# Z21_MEGA_2.net
KiCad netlist of a schematic drawn in EAGLE
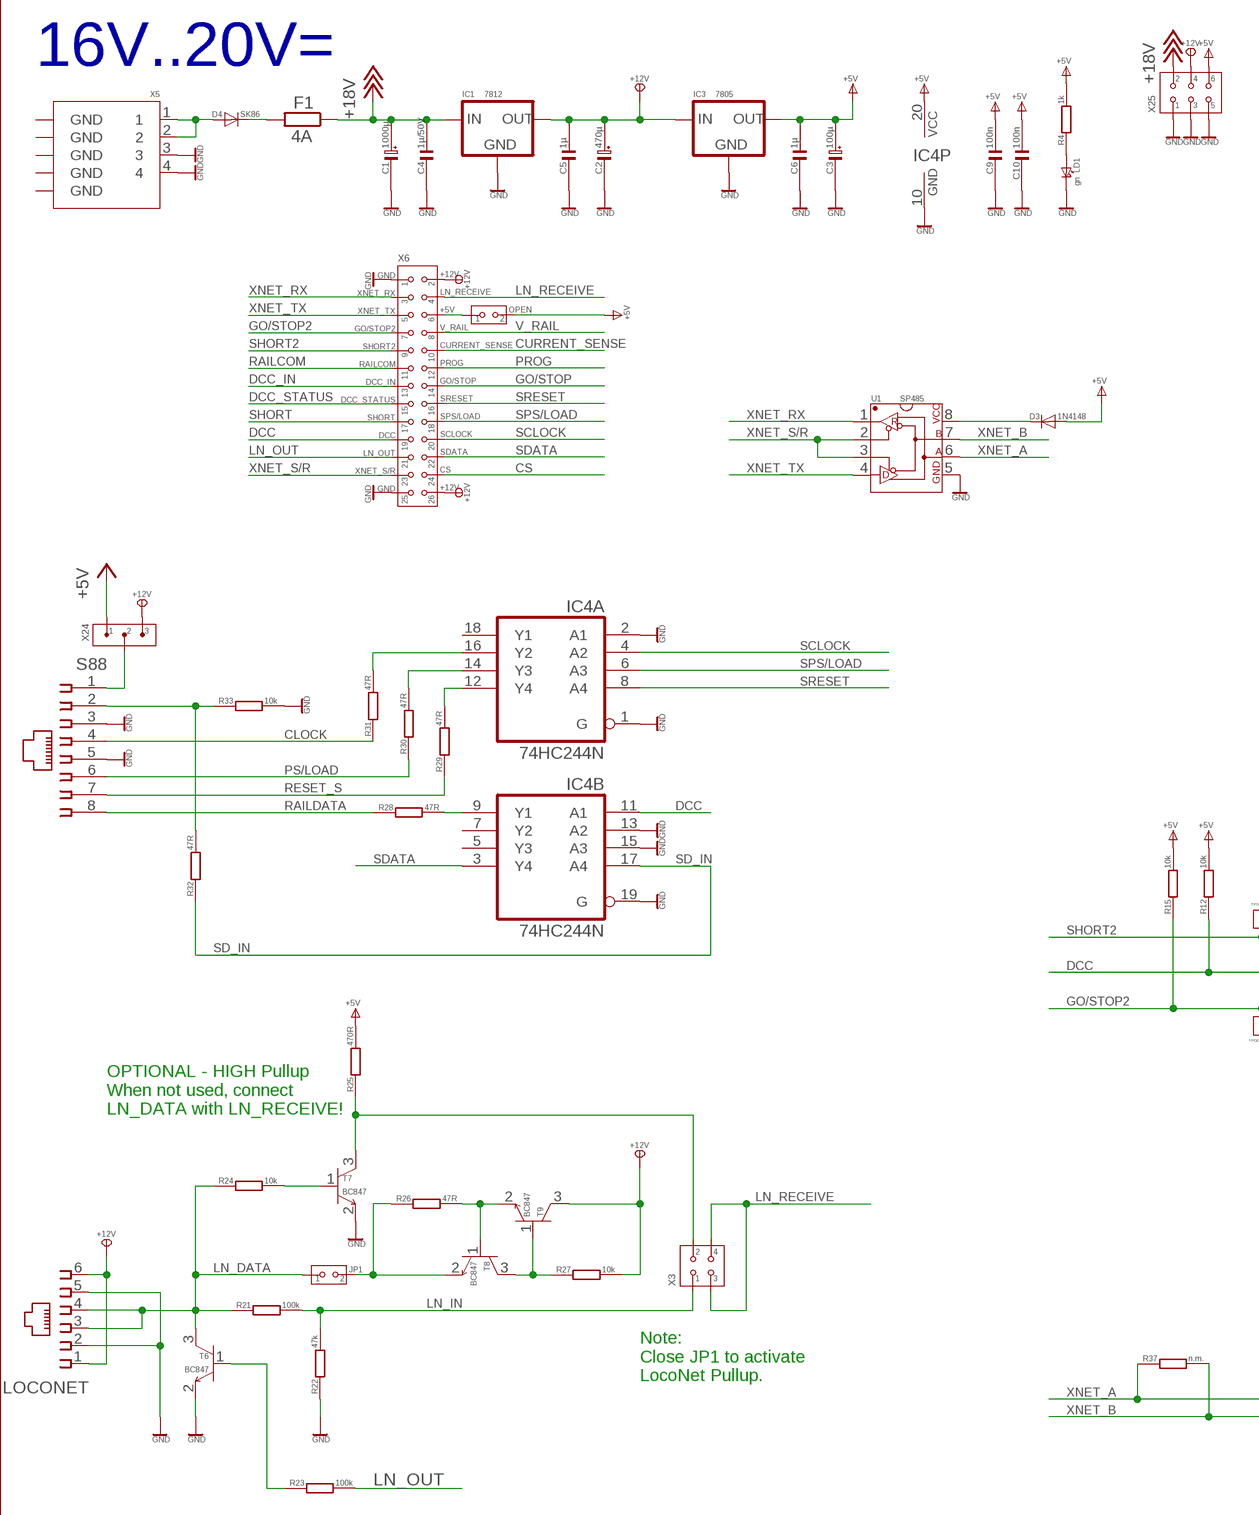
[diagram p0: schematic, sheet 1, part 1 of 2]
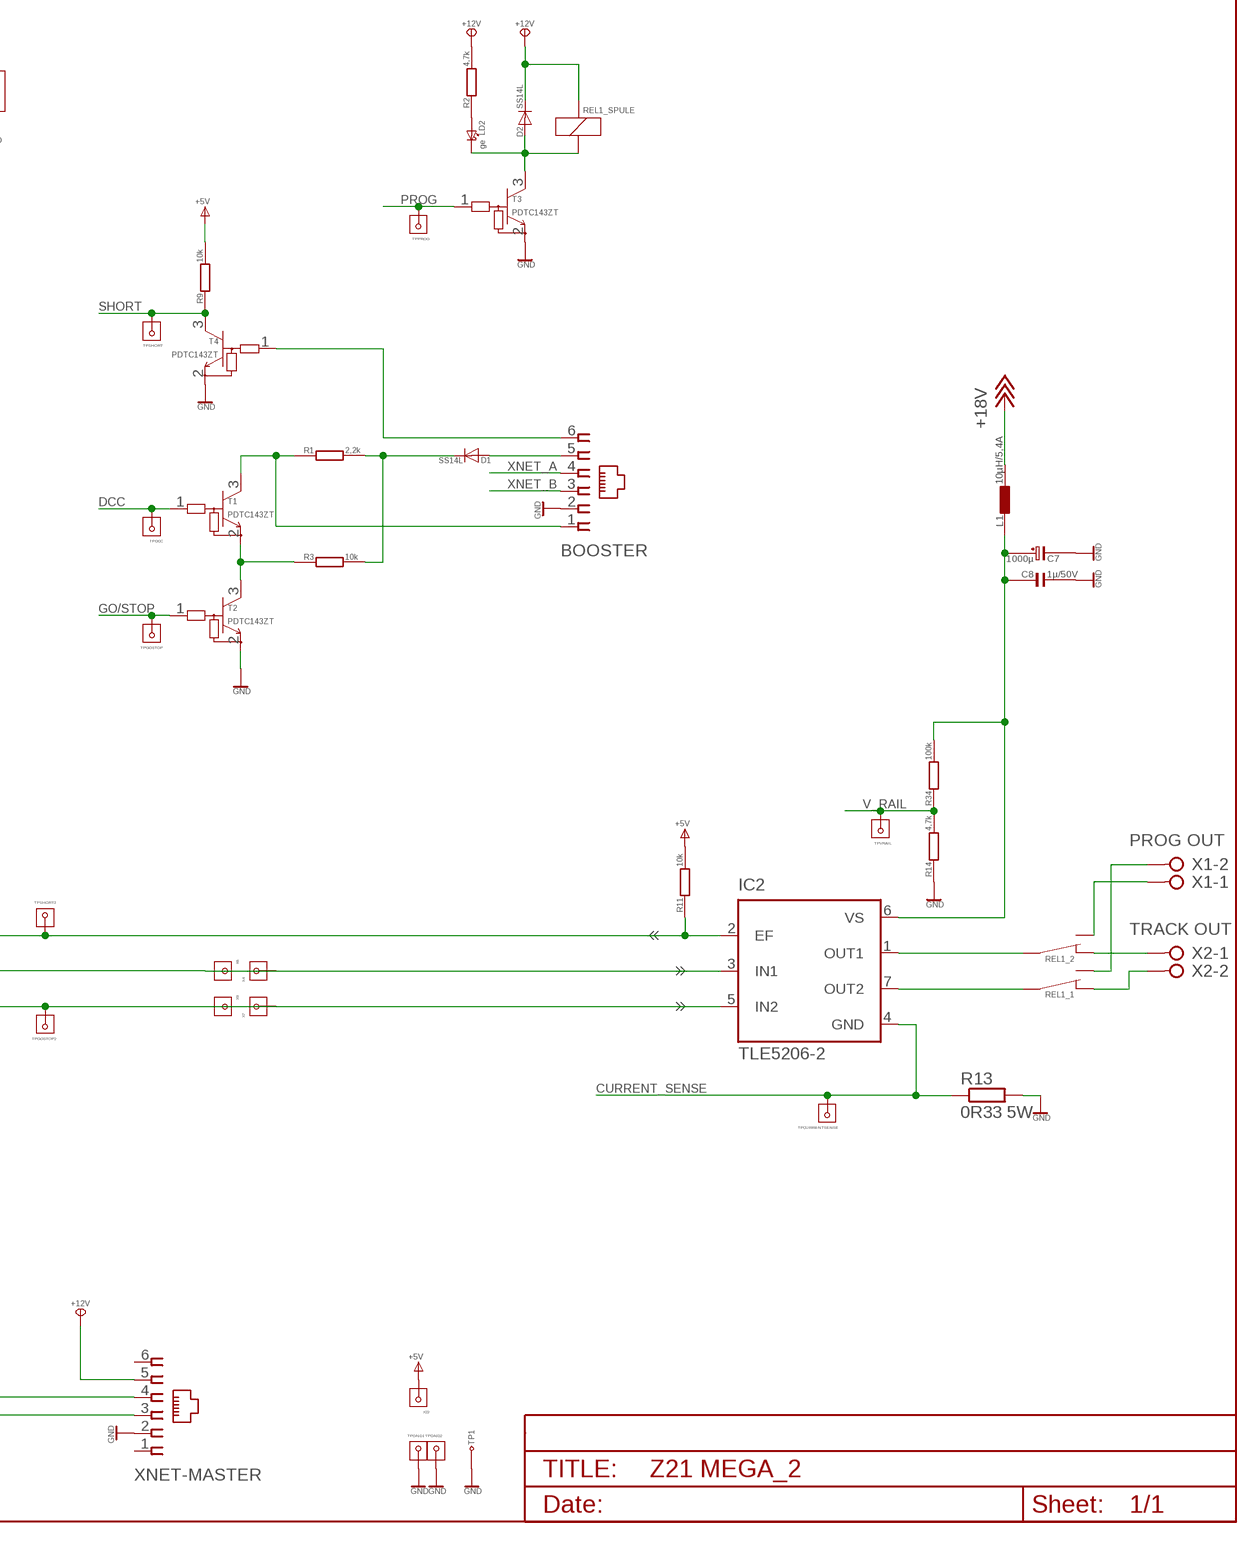
[diagram p1: schematic, sheet 1, part 2 of 2]

(export (version "E")
  (design (tool "Eeschema 10.0.6"))
  (components
    (comp (ref "BOOSTER")
      (value "520250-3")
      (footprint "eagle-import:520250-3")
      (libsource (lib "eagle-import") (part "520250-3"))
    )
    (comp (ref "C1")
      (value "1000µ")
      (footprint "eagle-import:RM5_DIA12.5")
      (libsource (lib "eagle-import") (part "ELKORM5_DIA12.5"))
    )
    (comp (ref "C2")
      (value "470µ")
      (footprint "eagle-import:RM5_DIA10")
      (libsource (lib "eagle-import") (part "ELKORM5_DIA10"))
    )
    (comp (ref "C3")
      (value "100µ")
      (footprint "eagle-import:RM2.5_DIA6")
      (libsource (lib "eagle-import") (part "ELKORM2.5_DIA6"))
    )
    (comp (ref "C4")
      (value "1µ/50V")
      (footprint "eagle-import:C0805")
      (libsource (lib "eagle-import") (part "C0805"))
    )
    (comp (ref "C5")
      (value "1µ")
      (footprint "eagle-import:C0805")
      (libsource (lib "eagle-import") (part "C0805"))
    )
    (comp (ref "C6")
      (value "1µ")
      (footprint "eagle-import:C0805")
      (libsource (lib "eagle-import") (part "C0805"))
    )
    (comp (ref "C7")
      (value "1000µ")
      (footprint "eagle-import:RM5_DIA12.5")
      (libsource (lib "eagle-import") (part "ELKORM5_DIA12.5"))
    )
    (comp (ref "C8")
      (value "1µ/50V")
      (footprint "eagle-import:C0805")
      (libsource (lib "eagle-import") (part "C0805"))
    )
    (comp (ref "C9")
      (value "100n")
      (footprint "eagle-import:C0805")
      (libsource (lib "eagle-import") (part "C0805"))
    )
    (comp (ref "C10")
      (value "100n")
      (footprint "eagle-import:C0805")
      (libsource (lib "eagle-import") (part "C0805"))
    )
    (comp (ref "D1")
      (value "SS14L")
      (footprint "eagle-import:SUB-SMA_")
      (libsource (lib "eagle-import") (part "DIODESUB-SMA_"))
    )
    (comp (ref "D2")
      (value "SS14L")
      (footprint "eagle-import:SUB-SMA_")
      (libsource (lib "eagle-import") (part "DIODESUB-SMA_"))
    )
    (comp (ref "D3")
      (value "1N4148")
      (footprint "eagle-import:SOD323_")
      (libsource (lib "eagle-import") (part "DIODESOD323"))
    )
    (comp (ref "D4")
      (value "SK86")
      (footprint "eagle-import:SMC_")
      (libsource (lib "eagle-import") (part "DIODESMC_"))
    )
    (comp (ref "F1")
      (value "4A")
      (footprint "eagle-import:0204_5")
      (libsource (lib "eagle-import") (part "R-EU_0204/5"))
    )
    (comp (ref "IC1")
      (value "7812")
      (footprint "eagle-import:78XXS")
      (libsource (lib "eagle-import") (part "78XXLSTEHEND"))
    )
    (comp (ref "IC2")
      (value "TLE5206-2")
      (footprint "eagle-import:P-TO220-7-11")
      (libsource (lib "eagle-import") (part "TLE5205-2"))
    )
    (comp (ref "IC3")
      (value "7805")
      (footprint "eagle-import:78XXS")
      (libsource (lib "eagle-import") (part "78XXLSTEHEND"))
    )
    (comp (ref "IC4")
      (value "74HC244N")
      (footprint "eagle-import:DIL20")
      (libsource (lib "eagle-import") (part "74244NHC"))
    )
    (comp (ref "JP1")
      (value "1X02_JUMPER_2.54MM")
      (footprint "eagle-import:1X02_2.54MM")
      (libsource (lib "eagle-import") (part "1X02_JUMPER_2.54MM"))
    )
    (comp (ref "L1")
      (value "10µH/5,4A")
      (footprint "eagle-import:12,5X12,5MM")
      (libsource (lib "eagle-import") (part "L12,5X12,5MM"))
    )
    (comp (ref "LD1")
      (value "gn")
      (footprint "eagle-import:LED3MM_")
      (libsource (lib "eagle-import") (part "LED3MM_"))
    )
    (comp (ref "LD2")
      (value "ge")
      (footprint "eagle-import:LED3MM_")
      (libsource (lib "eagle-import") (part "LED3MM_"))
    )
    (comp (ref "LOCONET")
      (value "520250-3")
      (footprint "eagle-import:520250-3")
      (libsource (lib "eagle-import") (part "520250-3"))
    )
    (comp (ref "OPEN")
      (value "1X02_JUMPER_2.54MM")
      (footprint "eagle-import:1X02_2.54MM")
      (libsource (lib "eagle-import") (part "1X02_JUMPER_2.54MM"))
    )
    (comp (ref "R1")
      (value "2,2k")
      (footprint "eagle-import:R0805")
      (libsource (lib "eagle-import") (part "R0805"))
    )
    (comp (ref "R2")
      (value "4,7k")
      (footprint "eagle-import:R0805")
      (libsource (lib "eagle-import") (part "R0805"))
    )
    (comp (ref "R3")
      (value "10k")
      (footprint "eagle-import:R0805")
      (libsource (lib "eagle-import") (part "R0805"))
    )
    (comp (ref "R4")
      (value "1k")
      (footprint "eagle-import:R0805")
      (libsource (lib "eagle-import") (part "R0805"))
    )
    (comp (ref "R9")
      (value "10k")
      (footprint "eagle-import:R0805")
      (libsource (lib "eagle-import") (part "R0805"))
    )
    (comp (ref "R11")
      (value "10k")
      (footprint "eagle-import:R0805")
      (libsource (lib "eagle-import") (part "R0805"))
    )
    (comp (ref "R12")
      (value "10k")
      (footprint "eagle-import:R0805")
      (libsource (lib "eagle-import") (part "R0805"))
    )
    (comp (ref "R13")
      (value "0R33 5W")
      (footprint "eagle-import:VMTA55")
      (libsource (lib "eagle-import") (part "R-EU_VMTA55"))
    )
    (comp (ref "R14")
      (value "4,7k")
      (footprint "eagle-import:R0805")
      (libsource (lib "eagle-import") (part "R0805"))
    )
    (comp (ref "R15")
      (value "10k")
      (footprint "eagle-import:R0805")
      (libsource (lib "eagle-import") (part "R0805"))
    )
    (comp (ref "R21")
      (value "100k")
      (footprint "eagle-import:R0805")
      (libsource (lib "eagle-import") (part "R0805"))
    )
    (comp (ref "R22")
      (value "47k")
      (footprint "eagle-import:R0805")
      (libsource (lib "eagle-import") (part "R0805"))
    )
    (comp (ref "R23")
      (value "100k")
      (footprint "eagle-import:R0805")
      (libsource (lib "eagle-import") (part "R0805"))
    )
    (comp (ref "R24")
      (value "10k")
      (footprint "eagle-import:R0805")
      (libsource (lib "eagle-import") (part "R0805"))
    )
    (comp (ref "R25")
      (value "470R")
      (footprint "eagle-import:R0805")
      (libsource (lib "eagle-import") (part "R0805"))
    )
    (comp (ref "R26")
      (value "47R")
      (footprint "eagle-import:R0805")
      (libsource (lib "eagle-import") (part "R0805"))
    )
    (comp (ref "R27")
      (value "10k")
      (footprint "eagle-import:R0805")
      (libsource (lib "eagle-import") (part "R0805"))
    )
    (comp (ref "R28")
      (value "47R")
      (footprint "eagle-import:R0805")
      (libsource (lib "eagle-import") (part "R0805"))
    )
    (comp (ref "R29")
      (value "47R")
      (footprint "eagle-import:R0805")
      (libsource (lib "eagle-import") (part "R0805"))
    )
    (comp (ref "R30")
      (value "47R")
      (footprint "eagle-import:R0805")
      (libsource (lib "eagle-import") (part "R0805"))
    )
    (comp (ref "R31")
      (value "47R")
      (footprint "eagle-import:R0805")
      (libsource (lib "eagle-import") (part "R0805"))
    )
    (comp (ref "R32")
      (value "47R")
      (footprint "eagle-import:R0805")
      (libsource (lib "eagle-import") (part "R0805"))
    )
    (comp (ref "R33")
      (value "10k")
      (footprint "eagle-import:R0805")
      (libsource (lib "eagle-import") (part "R0805"))
    )
    (comp (ref "R34")
      (value "100k")
      (footprint "eagle-import:R0805")
      (libsource (lib "eagle-import") (part "R0805"))
    )
    (comp (ref "R37")
      (value "n.m.")
      (footprint "eagle-import:R0805")
      (libsource (lib "eagle-import") (part "R0805"))
    )
    (comp (ref "REL1")
      (value "DIL16_1FINDER_40.527")
      (footprint "eagle-import:FINDER_40.527")
      (libsource (lib "eagle-import") (part "DIL16_1FINDER_40.527"))
    )
    (comp (ref "S88")
      (value "520251-4")
      (footprint "eagle-import:520251-4")
      (libsource (lib "eagle-import") (part "520251-4"))
    )
    (comp (ref "T1")
      (value "PDTC143ZT")
      (footprint "eagle-import:SOT23_")
      (libsource (lib "eagle-import") (part "NPN_PRE-BIASED"))
    )
    (comp (ref "T2")
      (value "PDTC143ZT")
      (footprint "eagle-import:SOT23_")
      (libsource (lib "eagle-import") (part "NPN_PRE-BIASED"))
    )
    (comp (ref "T3")
      (value "PDTC143ZT")
      (footprint "eagle-import:SOT23_")
      (libsource (lib "eagle-import") (part "NPN_PRE-BIASED"))
    )
    (comp (ref "T4")
      (value "PDTC143ZT")
      (footprint "eagle-import:SOT23_")
      (libsource (lib "eagle-import") (part "NPN_PRE-BIASED"))
    )
    (comp (ref "T6")
      (value "BC847")
      (footprint "eagle-import:SOT23_")
      (libsource (lib "eagle-import") (part "NPNSOT23"))
    )
    (comp (ref "T7")
      (value "BC847")
      (footprint "eagle-import:SOT23_")
      (libsource (lib "eagle-import") (part "NPNSOT23"))
    )
    (comp (ref "T8")
      (value "BC847")
      (footprint "eagle-import:SOT23_")
      (libsource (lib "eagle-import") (part "NPNSOT23"))
    )
    (comp (ref "T9")
      (value "BC847")
      (footprint "eagle-import:SOT23_")
      (libsource (lib "eagle-import") (part "NPNSOT23"))
    )
    (comp (ref "TP1")
      (value "LÖTPUNKTTHT_1.3MM_51.2MIL")
      (footprint "eagle-import:THT_1.3MM_51.2MIL")
      (libsource (lib "eagle-import") (part "LÖTPUNKTTHT_1.3MM_51.2MIL"))
    )
    (comp (ref "TPCURRENTSENSE")
      (value "1X01_2.54MM")
      (footprint "eagle-import:1X01_2.54MM")
      (libsource (lib "eagle-import") (part "1X01_2.54MM"))
    )
    (comp (ref "TPDCC")
      (value "1X01_2.54MM")
      (footprint "eagle-import:1X01_2.54MM")
      (libsource (lib "eagle-import") (part "1X01_2.54MM"))
    )
    (comp (ref "TPGND1")
      (value "1X01_2.54MM")
      (footprint "eagle-import:1X01_2.54MM")
      (libsource (lib "eagle-import") (part "1X01_2.54MM"))
    )
    (comp (ref "TPGND2")
      (value "1X01_2.54MM")
      (footprint "eagle-import:1X01_2.54MM")
      (libsource (lib "eagle-import") (part "1X01_2.54MM"))
    )
    (comp (ref "TPGOSTOP")
      (value "1X01_2.54MM")
      (footprint "eagle-import:1X01_2.54MM")
      (libsource (lib "eagle-import") (part "1X01_2.54MM"))
    )
    (comp (ref "TPGOSTOP2")
      (value "1X01_2.54MM")
      (footprint "eagle-import:1X01_2.54MM")
      (libsource (lib "eagle-import") (part "1X01_2.54MM"))
    )
    (comp (ref "TPPROG")
      (value "1X01_2.54MM")
      (footprint "eagle-import:1X01_2.54MM")
      (libsource (lib "eagle-import") (part "1X01_2.54MM"))
    )
    (comp (ref "TPSHORT")
      (value "1X01_2.54MM")
      (footprint "eagle-import:1X01_2.54MM")
      (libsource (lib "eagle-import") (part "1X01_2.54MM"))
    )
    (comp (ref "TPSHORT2")
      (value "1X01_2.54MM")
      (footprint "eagle-import:1X01_2.54MM")
      (libsource (lib "eagle-import") (part "1X01_2.54MM"))
    )
    (comp (ref "TPVRAIL")
      (value "1X01_2.54MM")
      (footprint "eagle-import:1X01_2.54MM")
      (libsource (lib "eagle-import") (part "1X01_2.54MM"))
    )
    (comp (ref "U1")
      (value "SP485")
      (footprint "eagle-import:SO8__")
      (libsource (lib "eagle-import") (part "MAX3485"))
    )
    (comp (ref "X1")
      (value "PROG OUT")
      (footprint "eagle-import:W237-132")
      (libsource (lib "eagle-import") (part "W237-02P"))
    )
    (comp (ref "X2")
      (value "TRACK OUT")
      (footprint "eagle-import:W237-132")
      (libsource (lib "eagle-import") (part "W237-02P"))
    )
    (comp (ref "X3")
      (value "2X02_2.54MM")
      (footprint "eagle-import:2X02_2.54MM")
      (libsource (lib "eagle-import") (part "2X02_2.54MM"))
    )
    (comp (ref "X4")
      (value "1X01_2.54MM")
      (footprint "eagle-import:1X01_2.54MM")
      (libsource (lib "eagle-import") (part "1X01_2.54MM"))
    )
    (comp (ref "X5")
      (value "MDINBU4-POWER")
      (footprint "eagle-import:MDINBU4-POWER")
      (libsource (lib "eagle-import") (part "MDINBU4-POWER"))
    )
    (comp (ref "X6")
      (value "2X13_WANNE_180°")
      (footprint "eagle-import:2X13_WANNE_180°")
      (libsource (lib "eagle-import") (part "2X13_WANNE_180°"))
    )
    (comp (ref "X7")
      (value "1X01_2.54MM")
      (footprint "eagle-import:1X01_2.54MM")
      (libsource (lib "eagle-import") (part "1X01_2.54MM"))
    )
    (comp (ref "X8")
      (value "1X01_2.54MM")
      (footprint "eagle-import:1X01_2.54MM")
      (libsource (lib "eagle-import") (part "1X01_2.54MM"))
    )
    (comp (ref "X9")
      (value "1X01_2.54MM")
      (footprint "eagle-import:1X01_2.54MM")
      (libsource (lib "eagle-import") (part "1X01_2.54MM"))
    )
    (comp (ref "X22")
      (value "1X01_2.54MM")
      (footprint "eagle-import:1X01_2.54MM")
      (libsource (lib "eagle-import") (part "1X01_2.54MM"))
    )
    (comp (ref "X24")
      (value "1X03T2,54MM")
      (footprint "eagle-import:1X03_2.54MM")
      (libsource (lib "eagle-import") (part "1X03T2,54MM"))
    )
    (comp (ref "X25")
      (value "2X03_2.54MM")
      (footprint "eagle-import:2X03_2.54MM")
      (libsource (lib "eagle-import") (part "2X03_2.54MM"))
    )
    (comp (ref "XNET-MASTER")
      (value "520250-3")
      (footprint "eagle-import:520250-3")
      (libsource (lib "eagle-import") (part "520250-3"))
    )
  )
  (nets
    (net (code "1") (name "+5V") (class "Default")
      (node (ref "C10") (pin "2") (pinfunction "P$2_2") (pintype "bidirectional"))
      (node (ref "C3") (pin "PLUS") (pinfunction "PLUS_PLUS") (pintype "bidirectional"))
      (node (ref "C6") (pin "2") (pinfunction "P$2_2") (pintype "bidirectional"))
      (node (ref "C9") (pin "2") (pinfunction "P$2_2") (pintype "bidirectional"))
      (node (ref "D3") (pin "ANODE") (pinfunction "ANODE_ANODE") (pintype "passive"))
      (node (ref "IC3") (pin "OUT") (pinfunction "OUT_OUT") (pintype "passive"))
      (node (ref "IC4") (pin "20") (pinfunction "VCC_20") (pintype "power_in"))
      (node (ref "OPEN") (pin "P$2") (pinfunction "P$2_P$2") (pintype "bidirectional"))
      (node (ref "R11") (pin "P$2") (pinfunction "P$2_P$2") (pintype "bidirectional"))
      (node (ref "R12") (pin "P$2") (pinfunction "P$2_P$2") (pintype "bidirectional"))
      (node (ref "R15") (pin "P$2") (pinfunction "P$2_P$2") (pintype "bidirectional"))
      (node (ref "R25") (pin "P$2") (pinfunction "P$2_P$2") (pintype "bidirectional"))
      (node (ref "R4") (pin "P$2") (pinfunction "P$2_P$2") (pintype "bidirectional"))
      (node (ref "R9") (pin "P$2") (pinfunction "P$2_P$2") (pintype "bidirectional"))
      (node (ref "X22") (pin "P$1") (pinfunction "P$1_P$1") (pintype "bidirectional"))
      (node (ref "X24") (pin "P$1") (pinfunction "P$1_P$1") (pintype "bidirectional"))
      (node (ref "X25") (pin "P$6") (pinfunction "P$6_P$6") (pintype "bidirectional"))
    )
    (net (code "2") (name "+12V") (class "Default")
      (node (ref "C2") (pin "PLUS") (pinfunction "PLUS_PLUS") (pintype "bidirectional"))
      (node (ref "C5") (pin "2") (pinfunction "P$2_2") (pintype "bidirectional"))
      (node (ref "D2") (pin "K") (pinfunction "KATHODE_K") (pintype "passive"))
      (node (ref "IC1") (pin "OUT") (pinfunction "OUT_OUT") (pintype "passive"))
      (node (ref "IC3") (pin "IN") (pinfunction "IN_IN") (pintype "input"))
      (node (ref "LOCONET") (pin "1") (pinfunction "1_1") (pintype "passive"))
      (node (ref "LOCONET") (pin "6") (pinfunction "6_6") (pintype "passive"))
      (node (ref "R2") (pin "P$2") (pinfunction "P$2_P$2") (pintype "bidirectional"))
      (node (ref "R27") (pin "P$2") (pinfunction "P$2_P$2") (pintype "bidirectional"))
      (node (ref "REL1") (pin "SP1") (pinfunction "+_SP1") (pintype "bidirectional"))
      (node (ref "T9") (pin "3") (pinfunction "C_3") (pintype "bidirectional"))
      (node (ref "X24") (pin "P$3") (pinfunction "P$3_P$3") (pintype "bidirectional"))
      (node (ref "X25") (pin "P$4") (pinfunction "P$4_P$4") (pintype "bidirectional"))
      (node (ref "X6") (pin "P$2") (pinfunction "P$2_P$2") (pintype "bidirectional"))
      (node (ref "X6") (pin "P$26") (pinfunction "P$26_P$26") (pintype "bidirectional"))
      (node (ref "XNET-MASTER") (pin "5") (pinfunction "5_5") (pintype "passive"))
    )
    (net (code "3") (name "+18V") (class "Default")
      (node (ref "C1") (pin "PLUS") (pinfunction "PLUS_PLUS") (pintype "bidirectional"))
      (node (ref "C4") (pin "2") (pinfunction "P$2_2") (pintype "bidirectional"))
      (node (ref "F1") (pin "1") (pinfunction "1_1") (pintype "passive"))
      (node (ref "IC1") (pin "IN") (pinfunction "IN_IN") (pintype "input"))
      (node (ref "L1") (pin "P$2") (pinfunction "P$2_P$2") (pintype "bidirectional"))
      (node (ref "X25") (pin "P$2") (pinfunction "P$2_P$2") (pintype "bidirectional"))
    )
    (net (code "4") (name "/CLOCK") (class "Default")
      (node (ref "R31") (pin "P$1") (pinfunction "P$1_P$1") (pintype "bidirectional"))
      (node (ref "S88") (pin "4") (pinfunction "4_4") (pintype "passive"))
    )
    (net (code "5") (name "/CS") (class "Default")
      (node (ref "X6") (pin "P$24") (pinfunction "P$24_P$24") (pintype "bidirectional"))
    )
    (net (code "6") (name "/CURRENT_SENSE") (class "Default")
      (node (ref "IC2") (pin "4") (pinfunction "GND_4") (pintype "power_in"))
      (node (ref "R13") (pin "1") (pinfunction "1_1") (pintype "passive"))
      (node (ref "TPCURRENTSENSE") (pin "P$1") (pinfunction "P$1_P$1") (pintype "bidirectional"))
      (node (ref "X6") (pin "P$10") (pinfunction "P$10_P$10") (pintype "bidirectional"))
    )
    (net (code "7") (name "/DCC") (class "Default")
      (node (ref "IC2") (pin "3") (pinfunction "IN1_3") (pintype "input"))
      (node (ref "IC4") (pin "11") (pinfunction "A1_11") (pintype "input"))
      (node (ref "R12") (pin "P$1") (pinfunction "P$1_P$1") (pintype "bidirectional"))
      (node (ref "T1") (pin "1") (pinfunction "B_1") (pintype "bidirectional"))
      (node (ref "TPDCC") (pin "P$1") (pinfunction "P$1_P$1") (pintype "bidirectional"))
      (node (ref "X4") (pin "P$1") (pinfunction "P$1_P$1") (pintype "bidirectional"))
      (node (ref "X6") (pin "P$19") (pinfunction "P$19_P$19") (pintype "bidirectional"))
      (node (ref "X8") (pin "P$1") (pinfunction "P$1_P$1") (pintype "bidirectional"))
    )
    (net (code "8") (name "/DCC_IN") (class "Default")
      (node (ref "X6") (pin "P$13") (pinfunction "P$13_P$13") (pintype "bidirectional"))
    )
    (net (code "9") (name "/DCC_STATUS") (class "Default")
      (node (ref "X6") (pin "P$15") (pinfunction "P$15_P$15") (pintype "bidirectional"))
    )
    (net (code "10") (name "/GO{slash}STOP") (class "Default")
      (node (ref "T2") (pin "1") (pinfunction "B_1") (pintype "bidirectional"))
      (node (ref "TPGOSTOP") (pin "P$1") (pinfunction "P$1_P$1") (pintype "bidirectional"))
      (node (ref "X6") (pin "P$14") (pinfunction "P$14_P$14") (pintype "bidirectional"))
    )
    (net (code "11") (name "/GO{slash}STOP2") (class "Default")
      (node (ref "IC2") (pin "5") (pinfunction "IN2_5") (pintype "input"))
      (node (ref "R15") (pin "P$1") (pinfunction "P$1_P$1") (pintype "bidirectional"))
      (node (ref "TPGOSTOP2") (pin "P$1") (pinfunction "P$1_P$1") (pintype "bidirectional"))
      (node (ref "X6") (pin "P$7") (pinfunction "P$7_P$7") (pintype "bidirectional"))
      (node (ref "X7") (pin "P$1") (pinfunction "P$1_P$1") (pintype "bidirectional"))
      (node (ref "X9") (pin "P$1") (pinfunction "P$1_P$1") (pintype "bidirectional"))
    )
    (net (code "12") (name "/LN_DATA") (class "Default")
      (node (ref "JP1") (pin "P$1") (pinfunction "P$1_P$1") (pintype "bidirectional"))
      (node (ref "LOCONET") (pin "3") (pinfunction "3_3") (pintype "passive"))
      (node (ref "LOCONET") (pin "4") (pinfunction "4_4") (pintype "passive"))
      (node (ref "R21") (pin "P$1") (pinfunction "P$1_P$1") (pintype "bidirectional"))
      (node (ref "R24") (pin "P$1") (pinfunction "P$1_P$1") (pintype "bidirectional"))
      (node (ref "T6") (pin "3") (pinfunction "C_3") (pintype "bidirectional"))
    )
    (net (code "13") (name "/LN_IN") (class "Default")
      (node (ref "R21") (pin "P$2") (pinfunction "P$2_P$2") (pintype "bidirectional"))
      (node (ref "R22") (pin "P$2") (pinfunction "P$2_P$2") (pintype "bidirectional"))
      (node (ref "X3") (pin "P$1") (pinfunction "P$1_P$1") (pintype "bidirectional"))
    )
    (net (code "14") (name "/LN_OUT") (class "Default")
      (node (ref "R23") (pin "P$2") (pinfunction "P$2_P$2") (pintype "bidirectional"))
      (node (ref "X6") (pin "P$21") (pinfunction "P$21_P$21") (pintype "bidirectional"))
    )
    (net (code "15") (name "/LN_RECEIVE") (class "Default")
      (node (ref "X3") (pin "P$3") (pinfunction "P$3_P$3") (pintype "bidirectional"))
      (node (ref "X3") (pin "P$4") (pinfunction "P$4_P$4") (pintype "bidirectional"))
      (node (ref "X6") (pin "P$4") (pinfunction "P$4_P$4") (pintype "bidirectional"))
    )
    (net (code "16") (name "/PROG") (class "Default")
      (node (ref "T3") (pin "1") (pinfunction "B_1") (pintype "bidirectional"))
      (node (ref "TPPROG") (pin "P$1") (pinfunction "P$1_P$1") (pintype "bidirectional"))
      (node (ref "X6") (pin "P$12") (pinfunction "P$12_P$12") (pintype "bidirectional"))
    )
    (net (code "17") (name "/PS{slash}LOAD") (class "Default")
      (node (ref "R30") (pin "P$1") (pinfunction "P$1_P$1") (pintype "bidirectional"))
      (node (ref "S88") (pin "6") (pinfunction "6_6") (pintype "passive"))
    )
    (net (code "18") (name "/RAILCOM") (class "Default")
      (node (ref "X6") (pin "P$11") (pinfunction "P$11_P$11") (pintype "bidirectional"))
    )
    (net (code "19") (name "/RAILDATA") (class "Default")
      (node (ref "R28") (pin "P$1") (pinfunction "P$1_P$1") (pintype "bidirectional"))
      (node (ref "S88") (pin "8") (pinfunction "8_8") (pintype "passive"))
    )
    (net (code "20") (name "/RESET_S") (class "Default")
      (node (ref "R29") (pin "P$1") (pinfunction "P$1_P$1") (pintype "bidirectional"))
      (node (ref "S88") (pin "7") (pinfunction "7_7") (pintype "passive"))
    )
    (net (code "21") (name "/SCLOCK") (class "Default")
      (node (ref "IC4") (pin "4") (pinfunction "A2_4") (pintype "input"))
      (node (ref "X6") (pin "P$20") (pinfunction "P$20_P$20") (pintype "bidirectional"))
    )
    (net (code "22") (name "/SDATA") (class "Default")
      (node (ref "IC4") (pin "3") (pinfunction "Y4_3") (pintype "tri_state"))
      (node (ref "X6") (pin "P$22") (pinfunction "P$22_P$22") (pintype "bidirectional"))
    )
    (net (code "23") (name "/SD_IN") (class "Default")
      (node (ref "IC4") (pin "17") (pinfunction "A4_17") (pintype "input"))
      (node (ref "R32") (pin "P$1") (pinfunction "P$1_P$1") (pintype "bidirectional"))
    )
    (net (code "24") (name "/SHORT") (class "Default")
      (node (ref "R9") (pin "P$1") (pinfunction "P$1_P$1") (pintype "bidirectional"))
      (node (ref "T4") (pin "3") (pinfunction "C_3") (pintype "bidirectional"))
      (node (ref "TPSHORT") (pin "P$1") (pinfunction "P$1_P$1") (pintype "bidirectional"))
      (node (ref "X6") (pin "P$17") (pinfunction "P$17_P$17") (pintype "bidirectional"))
    )
    (net (code "25") (name "/SHORT2") (class "Default")
      (node (ref "IC2") (pin "2") (pinfunction "EF_2") (pintype "open_collector"))
      (node (ref "R11") (pin "P$1") (pinfunction "P$1_P$1") (pintype "bidirectional"))
      (node (ref "TPSHORT2") (pin "P$1") (pinfunction "P$1_P$1") (pintype "bidirectional"))
      (node (ref "X6") (pin "P$9") (pinfunction "P$9_P$9") (pintype "bidirectional"))
    )
    (net (code "26") (name "/SPS{slash}LOAD") (class "Default")
      (node (ref "IC4") (pin "6") (pinfunction "A3_6") (pintype "input"))
      (node (ref "X6") (pin "P$18") (pinfunction "P$18_P$18") (pintype "bidirectional"))
    )
    (net (code "27") (name "/SRESET") (class "Default")
      (node (ref "IC4") (pin "8") (pinfunction "A4_8") (pintype "input"))
      (node (ref "X6") (pin "P$16") (pinfunction "P$16_P$16") (pintype "bidirectional"))
    )
    (net (code "28") (name "/V_RAIL") (class "Default")
      (node (ref "R14") (pin "P$2") (pinfunction "P$2_P$2") (pintype "bidirectional"))
      (node (ref "R34") (pin "P$1") (pinfunction "P$1_P$1") (pintype "bidirectional"))
      (node (ref "TPVRAIL") (pin "P$1") (pinfunction "P$1_P$1") (pintype "bidirectional"))
      (node (ref "X6") (pin "P$8") (pinfunction "P$8_P$8") (pintype "bidirectional"))
    )
    (net (code "29") (name "/XNET_A") (class "Default")
      (node (ref "BOOSTER") (pin "4") (pinfunction "4_4") (pintype "passive"))
      (node (ref "R37") (pin "P$1") (pinfunction "P$1_P$1") (pintype "bidirectional"))
      (node (ref "U1") (pin "6") (pinfunction "P$6_6") (pintype "bidirectional"))
      (node (ref "XNET-MASTER") (pin "4") (pinfunction "4_4") (pintype "passive"))
    )
    (net (code "30") (name "/XNET_B") (class "Default")
      (node (ref "BOOSTER") (pin "3") (pinfunction "3_3") (pintype "passive"))
      (node (ref "R37") (pin "P$2") (pinfunction "P$2_P$2") (pintype "bidirectional"))
      (node (ref "U1") (pin "7") (pinfunction "P$7_7") (pintype "bidirectional"))
      (node (ref "XNET-MASTER") (pin "3") (pinfunction "3_3") (pintype "passive"))
    )
    (net (code "31") (name "/XNET_RX") (class "Default")
      (node (ref "U1") (pin "1") (pinfunction "P$1_1") (pintype "bidirectional"))
      (node (ref "X6") (pin "P$3") (pinfunction "P$3_P$3") (pintype "bidirectional"))
    )
    (net (code "32") (name "/XNET_S{slash}R") (class "Default")
      (node (ref "U1") (pin "2") (pinfunction "P$2_2") (pintype "bidirectional"))
      (node (ref "U1") (pin "3") (pinfunction "P$3_3") (pintype "bidirectional"))
      (node (ref "X6") (pin "P$23") (pinfunction "P$23_P$23") (pintype "bidirectional"))
    )
    (net (code "33") (name "/XNET_TX") (class "Default")
      (node (ref "U1") (pin "4") (pinfunction "P$4_4") (pintype "bidirectional"))
      (node (ref "X6") (pin "P$5") (pinfunction "P$5_P$5") (pintype "bidirectional"))
    )
    (net (code "34") (name "GND") (class "Default")
      (node (ref "BOOSTER") (pin "2") (pinfunction "2_2") (pintype "passive"))
      (node (ref "C1") (pin "MINUS") (pinfunction "MINUS_MINUS") (pintype "bidirectional"))
      (node (ref "C10") (pin "1") (pinfunction "P$1_1") (pintype "bidirectional"))
      (node (ref "C2") (pin "MINUS") (pinfunction "MINUS_MINUS") (pintype "bidirectional"))
      (node (ref "C3") (pin "MINUS") (pinfunction "MINUS_MINUS") (pintype "bidirectional"))
      (node (ref "C4") (pin "1") (pinfunction "P$1_1") (pintype "bidirectional"))
      (node (ref "C5") (pin "1") (pinfunction "P$1_1") (pintype "bidirectional"))
      (node (ref "C6") (pin "1") (pinfunction "P$1_1") (pintype "bidirectional"))
      (node (ref "C7") (pin "MINUS") (pinfunction "MINUS_MINUS") (pintype "bidirectional"))
      (node (ref "C8") (pin "2") (pinfunction "P$2_2") (pintype "bidirectional"))
      (node (ref "C9") (pin "1") (pinfunction "P$1_1") (pintype "bidirectional"))
      (node (ref "IC1") (pin "GND") (pinfunction "GND_GND") (pintype "input"))
      (node (ref "IC3") (pin "GND") (pinfunction "GND_GND") (pintype "input"))
      (node (ref "IC4") (pin "1") (pinfunction "G_1") (pintype "input"))
      (node (ref "IC4") (pin "10") (pinfunction "GND_10") (pintype "power_in"))
      (node (ref "IC4") (pin "13") (pinfunction "A2_13") (pintype "input"))
      (node (ref "IC4") (pin "15") (pinfunction "A3_15") (pintype "input"))
      (node (ref "IC4") (pin "19") (pinfunction "G_19") (pintype "input"))
      (node (ref "IC4") (pin "2") (pinfunction "A1_2") (pintype "input"))
      (node (ref "LD1") (pin "K") (pinfunction "KATHODE_K") (pintype "bidirectional"))
      (node (ref "LOCONET") (pin "2") (pinfunction "2_2") (pintype "passive"))
      (node (ref "LOCONET") (pin "5") (pinfunction "5_5") (pintype "passive"))
      (node (ref "R13") (pin "2") (pinfunction "2_2") (pintype "passive"))
      (node (ref "R14") (pin "P$1") (pinfunction "P$1_P$1") (pintype "bidirectional"))
      (node (ref "R22") (pin "P$1") (pinfunction "P$1_P$1") (pintype "bidirectional"))
      (node (ref "R33") (pin "P$2") (pinfunction "P$2_P$2") (pintype "bidirectional"))
      (node (ref "S88") (pin "3") (pinfunction "3_3") (pintype "passive"))
      (node (ref "S88") (pin "5") (pinfunction "5_5") (pintype "passive"))
      (node (ref "T2") (pin "2") (pinfunction "E_2") (pintype "bidirectional"))
      (node (ref "T3") (pin "2") (pinfunction "E_2") (pintype "bidirectional"))
      (node (ref "T4") (pin "2") (pinfunction "E_2") (pintype "bidirectional"))
      (node (ref "T6") (pin "2") (pinfunction "E_2") (pintype "bidirectional"))
      (node (ref "T7") (pin "2") (pinfunction "E_2") (pintype "bidirectional"))
      (node (ref "TP1") (pin "P$1") (pinfunction "P$1_P$1") (pintype "bidirectional"))
      (node (ref "TPGND1") (pin "P$1") (pinfunction "P$1_P$1") (pintype "bidirectional"))
      (node (ref "TPGND2") (pin "P$1") (pinfunction "P$1_P$1") (pintype "bidirectional"))
      (node (ref "U1") (pin "5") (pinfunction "P$5_5") (pintype "bidirectional"))
      (node (ref "X25") (pin "P$1") (pinfunction "P$1_P$1") (pintype "bidirectional"))
      (node (ref "X25") (pin "P$3") (pinfunction "P$3_P$3") (pintype "bidirectional"))
      (node (ref "X25") (pin "P$5") (pinfunction "P$5_P$5") (pintype "bidirectional"))
      (node (ref "X5") (pin "3") (pinfunction "3_3") (pintype "bidirectional"))
      (node (ref "X5") (pin "4") (pinfunction "4_4") (pintype "bidirectional"))
      (node (ref "X6") (pin "P$1") (pinfunction "P$1_P$1") (pintype "bidirectional"))
      (node (ref "X6") (pin "P$25") (pinfunction "P$25_P$25") (pintype "bidirectional"))
      (node (ref "XNET-MASTER") (pin "2") (pinfunction "2_2") (pintype "passive"))
    )
    (net (code "35") (name "Net-(C8-P$1)") (class "Default")
      (node (ref "C7") (pin "PLUS") (pinfunction "PLUS_PLUS") (pintype "bidirectional"))
      (node (ref "C8") (pin "1") (pinfunction "P$1_1") (pintype "bidirectional"))
      (node (ref "IC2") (pin "6") (pinfunction "VS_6") (pintype "input"))
      (node (ref "L1") (pin "P$1") (pinfunction "P$1_P$1") (pintype "bidirectional"))
      (node (ref "R34") (pin "P$2") (pinfunction "P$2_P$2") (pintype "bidirectional"))
    )
    (net (code "36") (name "Net-(D1-ANODE)") (class "Default")
      (node (ref "BOOSTER") (pin "5") (pinfunction "5_5") (pintype "passive"))
      (node (ref "D1") (pin "A") (pinfunction "ANODE_A") (pintype "passive"))
    )
    (net (code "37") (name "Net-(D1-KATHODE)") (class "Default")
      (node (ref "D1") (pin "K") (pinfunction "KATHODE_K") (pintype "passive"))
      (node (ref "R1") (pin "P$2") (pinfunction "P$2_P$2") (pintype "bidirectional"))
      (node (ref "R3") (pin "P$2") (pinfunction "P$2_P$2") (pintype "bidirectional"))
    )
    (net (code "38") (name "Net-(D2-ANODE)") (class "Default")
      (node (ref "D2") (pin "A") (pinfunction "ANODE_A") (pintype "passive"))
      (node (ref "LD2") (pin "K") (pinfunction "KATHODE_K") (pintype "bidirectional"))
      (node (ref "REL1") (pin "SP2") (pinfunction "-_SP2") (pintype "bidirectional"))
      (node (ref "T3") (pin "3") (pinfunction "C_3") (pintype "bidirectional"))
    )
    (net (code "39") (name "Net-(D4-ANODE)") (class "Default")
      (node (ref "D4") (pin "A") (pinfunction "ANODE_A") (pintype "passive"))
      (node (ref "X5") (pin "1") (pinfunction "1_1") (pintype "bidirectional"))
      (node (ref "X5") (pin "2") (pinfunction "2_2") (pintype "bidirectional"))
    )
    (net (code "40") (name "Net-(D4-KATHODE)") (class "Default")
      (node (ref "D4") (pin "K") (pinfunction "KATHODE_K") (pintype "passive"))
      (node (ref "F1") (pin "2") (pinfunction "2_2") (pintype "passive"))
    )
    (net (code "41") (name "Net-(IC2-OUT1)") (class "Default")
      (node (ref "IC2") (pin "1") (pinfunction "OUT1_1") (pintype "output"))
      (node (ref "REL1") (pin "P2") (pinfunction "P_P2") (pintype "bidirectional"))
    )
    (net (code "42") (name "Net-(IC2-OUT2)") (class "Default")
      (node (ref "IC2") (pin "7") (pinfunction "OUT2_7") (pintype "output"))
      (node (ref "REL1") (pin "P1") (pinfunction "P_P1") (pintype "bidirectional"))
    )
    (net (code "43") (name "Net-(IC4A-Y2)") (class "Default")
      (node (ref "IC4") (pin "16") (pinfunction "Y2_16") (pintype "tri_state"))
      (node (ref "R31") (pin "P$2") (pinfunction "P$2_P$2") (pintype "bidirectional"))
    )
    (net (code "44") (name "Net-(IC4A-Y3)") (class "Default")
      (node (ref "IC4") (pin "14") (pinfunction "Y3_14") (pintype "tri_state"))
      (node (ref "R30") (pin "P$2") (pinfunction "P$2_P$2") (pintype "bidirectional"))
    )
    (net (code "45") (name "Net-(IC4A-Y4)") (class "Default")
      (node (ref "IC4") (pin "12") (pinfunction "Y4_12") (pintype "tri_state"))
      (node (ref "R29") (pin "P$2") (pinfunction "P$2_P$2") (pintype "bidirectional"))
    )
    (net (code "46") (name "Net-(IC4B-Y1)") (class "Default")
      (node (ref "IC4") (pin "9") (pinfunction "Y1_9") (pintype "tri_state"))
      (node (ref "R28") (pin "P$2") (pinfunction "P$2_P$2") (pintype "bidirectional"))
    )
    (net (code "47") (name "Net-(LD1-ANODE)") (class "Default")
      (node (ref "LD1") (pin "A") (pinfunction "ANODE_A") (pintype "bidirectional"))
      (node (ref "R4") (pin "P$1") (pinfunction "P$1_P$1") (pintype "bidirectional"))
    )
    (net (code "48") (name "Net-(LD2-ANODE)") (class "Default")
      (node (ref "LD2") (pin "A") (pinfunction "ANODE_A") (pintype "bidirectional"))
      (node (ref "R2") (pin "P$1") (pinfunction "P$1_P$1") (pintype "bidirectional"))
    )
    (net (code "49") (name "Net-(OPEN-PadP$1)") (class "Default")
      (node (ref "OPEN") (pin "P$1") (pinfunction "P$1_P$1") (pintype "bidirectional"))
      (node (ref "X6") (pin "P$6") (pinfunction "P$6_P$6") (pintype "bidirectional"))
    )
    (net (code "50") (name "Net-(R32-PadP$2)") (class "Default")
      (node (ref "R32") (pin "P$2") (pinfunction "P$2_P$2") (pintype "bidirectional"))
      (node (ref "R33") (pin "P$1") (pinfunction "P$1_P$1") (pintype "bidirectional"))
      (node (ref "S88") (pin "2") (pinfunction "2_2") (pintype "passive"))
    )
    (net (code "51") (name "Net-(REL1A-S)") (class "Default")
      (node (ref "REL1") (pin "S1") (pinfunction "S_S1") (pintype "bidirectional"))
      (node (ref "X1") (pin "2") (pinfunction "KL_2") (pintype "passive"))
    )
    (net (code "52") (name "Net-(REL1A-Ö)") (class "Default")
      (node (ref "REL1") (pin "Ö1") (pinfunction "Ö_Ö1") (pintype "bidirectional"))
      (node (ref "X2") (pin "2") (pinfunction "KL_2") (pintype "passive"))
    )
    (net (code "53") (name "Net-(REL1B-S)") (class "Default")
      (node (ref "REL1") (pin "S2") (pinfunction "S_S2") (pintype "bidirectional"))
      (node (ref "X1") (pin "1") (pinfunction "KL_1") (pintype "passive"))
    )
    (net (code "54") (name "Net-(REL1B-Ö)") (class "Default")
      (node (ref "REL1") (pin "Ö2") (pinfunction "Ö_Ö2") (pintype "bidirectional"))
      (node (ref "X2") (pin "1") (pinfunction "KL_1") (pintype "passive"))
    )
    (net (code "55") (name "Net-(S88-Pad1)") (class "Default")
      (node (ref "S88") (pin "1") (pinfunction "1_1") (pintype "passive"))
      (node (ref "X24") (pin "P$2") (pinfunction "P$2_P$2") (pintype "bidirectional"))
    )
    (net (code "56") (name "Net-(T1-C)") (class "Default")
      (node (ref "BOOSTER") (pin "1") (pinfunction "1_1") (pintype "passive"))
      (node (ref "R1") (pin "P$1") (pinfunction "P$1_P$1") (pintype "bidirectional"))
      (node (ref "T1") (pin "3") (pinfunction "C_3") (pintype "bidirectional"))
    )
    (net (code "57") (name "Net-(T1-E)") (class "Default")
      (node (ref "R3") (pin "P$1") (pinfunction "P$1_P$1") (pintype "bidirectional"))
      (node (ref "T1") (pin "2") (pinfunction "E_2") (pintype "bidirectional"))
      (node (ref "T2") (pin "3") (pinfunction "C_3") (pintype "bidirectional"))
    )
    (net (code "58") (name "Net-(T4-B)") (class "Default")
      (node (ref "BOOSTER") (pin "6") (pinfunction "6_6") (pintype "passive"))
      (node (ref "T4") (pin "1") (pinfunction "B_1") (pintype "bidirectional"))
    )
    (net (code "59") (name "Net-(T6-B)") (class "Default")
      (node (ref "R23") (pin "P$1") (pinfunction "P$1_P$1") (pintype "bidirectional"))
      (node (ref "T6") (pin "1") (pinfunction "B_1") (pintype "bidirectional"))
    )
    (net (code "60") (name "Net-(T7-B)") (class "Default")
      (node (ref "R24") (pin "P$2") (pinfunction "P$2_P$2") (pintype "bidirectional"))
      (node (ref "T7") (pin "1") (pinfunction "B_1") (pintype "bidirectional"))
    )
    (net (code "61") (name "Net-(T7-C)") (class "Default")
      (node (ref "R25") (pin "P$1") (pinfunction "P$1_P$1") (pintype "bidirectional"))
      (node (ref "T7") (pin "3") (pinfunction "C_3") (pintype "bidirectional"))
      (node (ref "X3") (pin "P$2") (pinfunction "P$2_P$2") (pintype "bidirectional"))
    )
    (net (code "62") (name "Net-(T8-B)") (class "Default")
      (node (ref "R26") (pin "P$2") (pinfunction "P$2_P$2") (pintype "bidirectional"))
      (node (ref "T8") (pin "1") (pinfunction "B_1") (pintype "bidirectional"))
      (node (ref "T9") (pin "2") (pinfunction "E_2") (pintype "bidirectional"))
    )
    (net (code "63") (name "Net-(T8-C)") (class "Default")
      (node (ref "R27") (pin "P$1") (pinfunction "P$1_P$1") (pintype "bidirectional"))
      (node (ref "T8") (pin "3") (pinfunction "C_3") (pintype "bidirectional"))
      (node (ref "T9") (pin "1") (pinfunction "B_1") (pintype "bidirectional"))
    )
    (net (code "64") (name "Net-(T8-E)") (class "Default")
      (node (ref "JP1") (pin "P$2") (pinfunction "P$2_P$2") (pintype "bidirectional"))
      (node (ref "R26") (pin "P$1") (pinfunction "P$1_P$1") (pintype "bidirectional"))
      (node (ref "T8") (pin "2") (pinfunction "E_2") (pintype "bidirectional"))
    )
    (net (code "65") (name "Net-(U1-P$8)") (class "Default")
      (node (ref "D3") (pin "KATHODE") (pinfunction "KATHODE_KATHODE") (pintype "passive"))
      (node (ref "U1") (pin "8") (pinfunction "P$8_8") (pintype "bidirectional"))
    )
    (net (code "66") (name "unconnected-(IC4A-Y1-Pad18)") (class "Default")
      (node (ref "IC4") (pin "18") (pinfunction "Y1_18") (pintype "tri_state"))
    )
    (net (code "67") (name "unconnected-(IC4B-Y2-Pad7)") (class "Default")
      (node (ref "IC4") (pin "7") (pinfunction "Y2_7") (pintype "tri_state"))
    )
    (net (code "68") (name "unconnected-(IC4B-Y3-Pad5)") (class "Default")
      (node (ref "IC4") (pin "5") (pinfunction "Y3_5") (pintype "tri_state"))
    )
    (net (code "69") (name "unconnected-(X5-GND-PadGND@1)") (class "Default")
      (node (ref "X5") (pin "GND@1") (pinfunction "GND_GND@1") (pintype "bidirectional"))
    )
    (net (code "70") (name "unconnected-(X5-GND-PadGND@2)") (class "Default")
      (node (ref "X5") (pin "GND@2") (pinfunction "GND_GND@2") (pintype "bidirectional"))
    )
    (net (code "71") (name "unconnected-(X5-GND-PadGND@3)") (class "Default")
      (node (ref "X5") (pin "GND@3") (pinfunction "GND_GND@3") (pintype "bidirectional"))
    )
    (net (code "72") (name "unconnected-(X5-GND-PadGND@4)") (class "Default")
      (node (ref "X5") (pin "GND@4") (pinfunction "GND_GND@4") (pintype "bidirectional"))
    )
    (net (code "73") (name "unconnected-(X5-GND-PadGND@5)") (class "Default")
      (node (ref "X5") (pin "GND@5") (pinfunction "GND_GND@5") (pintype "bidirectional"))
    )
    (net (code "74") (name "unconnected-(XNET-MASTER-Pad1)") (class "Default")
      (node (ref "XNET-MASTER") (pin "1") (pinfunction "1_1") (pintype "passive"))
    )
    (net (code "75") (name "unconnected-(XNET-MASTER-Pad6)") (class "Default")
      (node (ref "XNET-MASTER") (pin "6") (pinfunction "6_6") (pintype "passive"))
    )
  )
)
